# main2.net
KiCad netlist of a schematic drawn in EAGLE
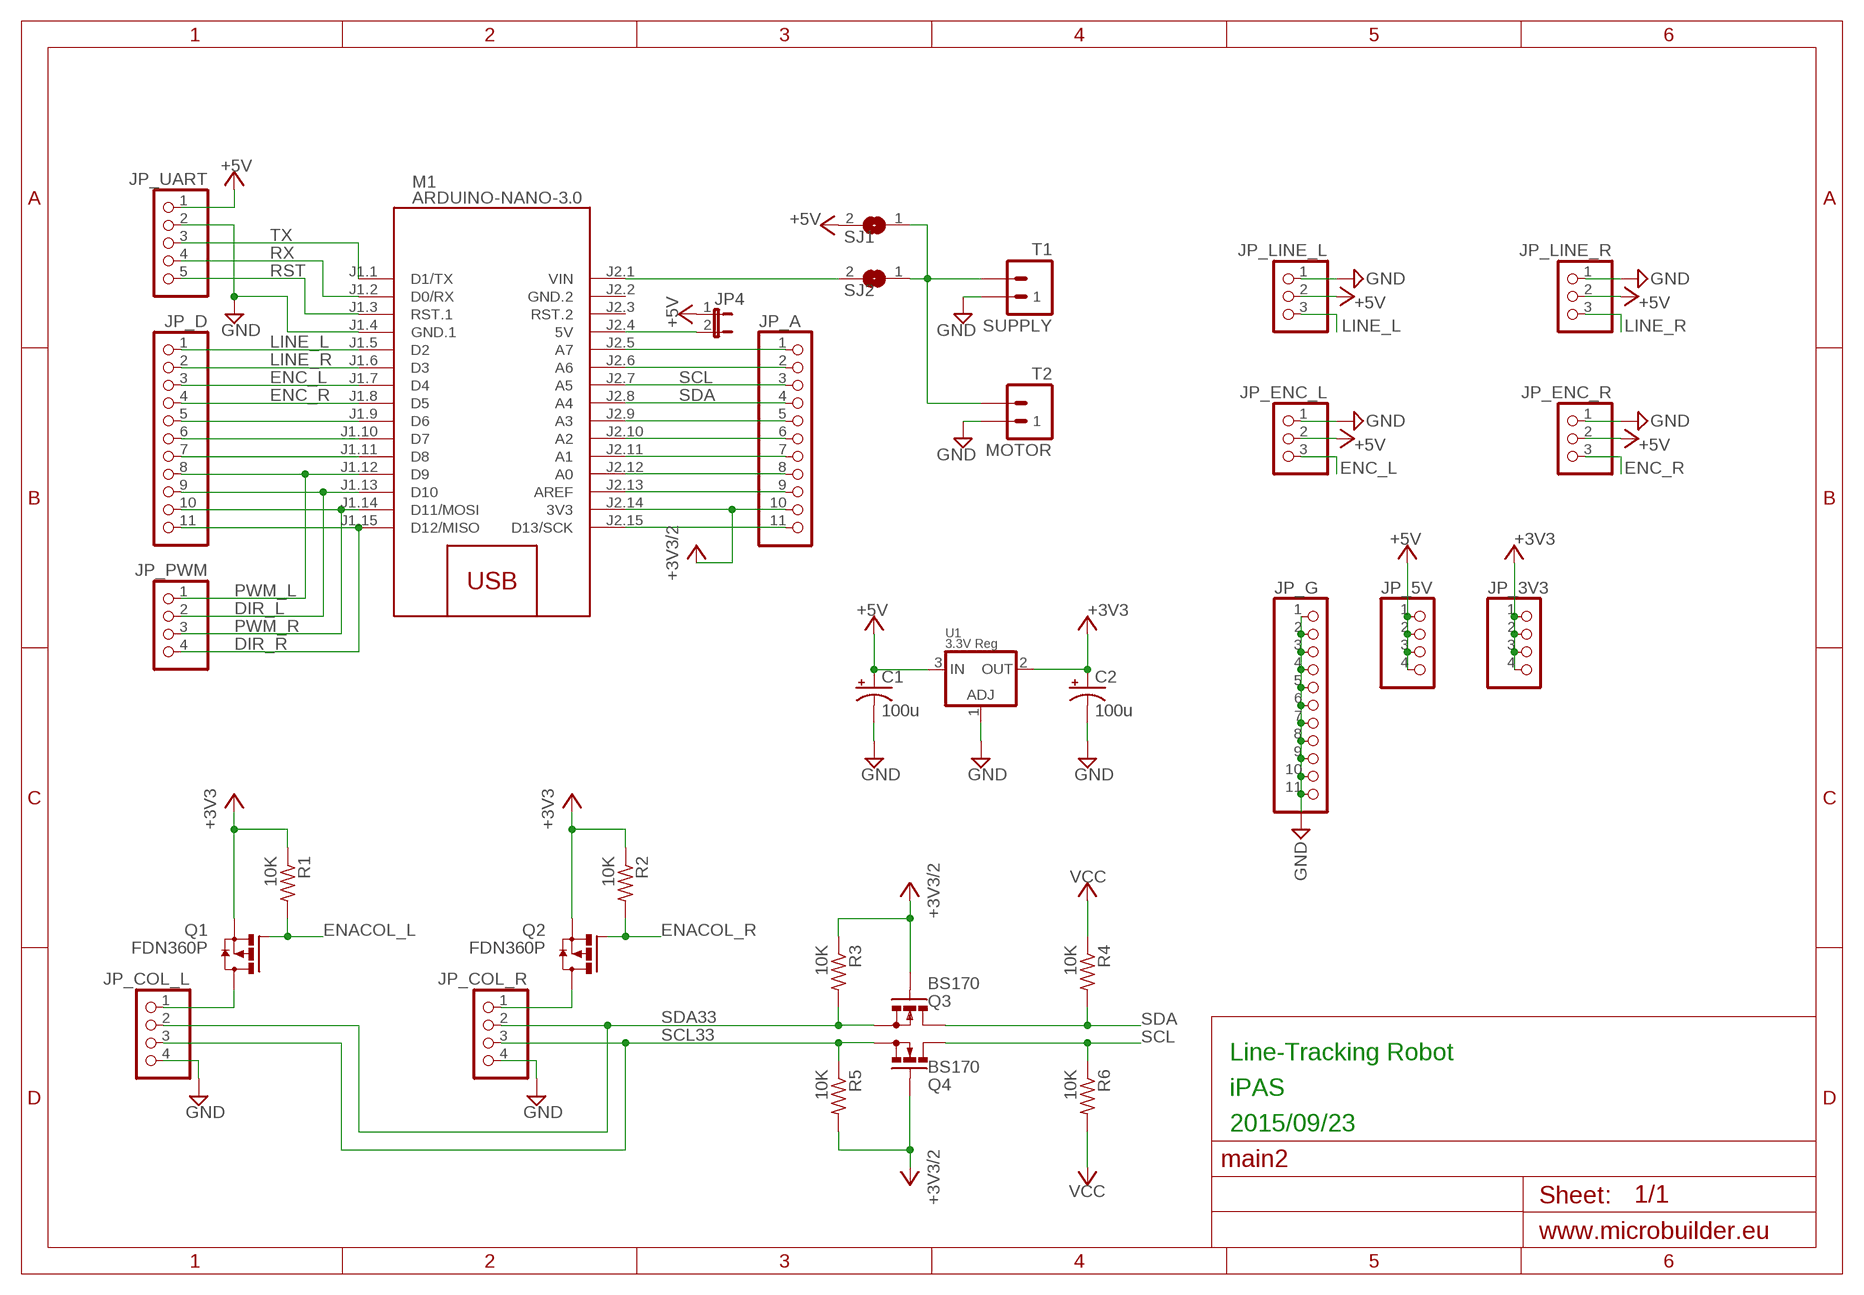
[diagram p0: schematic, sheet 1]

(export (version "E")
  (design (tool "Eeschema 10.0.6"))
  (components
    (comp (ref "C1")
      (value "100u")
      (footprint "eagle-import:RCL_E2,5-6")
      (libsource (lib "eagle-import") (part "RCL_CPOL-USE2.5-6"))
    )
    (comp (ref "C2")
      (value "100u")
      (footprint "eagle-import:RCL_E2,5-6")
      (libsource (lib "eagle-import") (part "RCL_CPOL-USE2.5-6"))
    )
    (comp (ref "JP4")
      (value "JUMPER2")
      (footprint "eagle-import:JUMPER2")
      (libsource (lib "eagle-import") (part "JUMPER2"))
    )
    (comp (ref "JP_3V3")
      (value "HEADER-1X4ROUND")
      (footprint "eagle-import:1X04_ROUND")
      (libsource (lib "eagle-import") (part "HEADER-1X4ROUND"))
    )
    (comp (ref "JP_5V")
      (value "HEADER-1X4ROUND")
      (footprint "eagle-import:1X04_ROUND")
      (libsource (lib "eagle-import") (part "HEADER-1X4ROUND"))
    )
    (comp (ref "JP_A")
      (value "HEADER-1X11")
      (footprint "eagle-import:1X11_ROUND")
      (libsource (lib "eagle-import") (part "HEADER-1X11"))
    )
    (comp (ref "JP_COL_L")
      (value "HEADER-1X4ROUND")
      (footprint "eagle-import:1X04_ROUND")
      (libsource (lib "eagle-import") (part "HEADER-1X4ROUND"))
    )
    (comp (ref "JP_COL_R")
      (value "HEADER-1X4ROUND")
      (footprint "eagle-import:1X04_ROUND")
      (libsource (lib "eagle-import") (part "HEADER-1X4ROUND"))
    )
    (comp (ref "JP_D")
      (value "HEADER-1X11")
      (footprint "eagle-import:1X11_ROUND")
      (libsource (lib "eagle-import") (part "HEADER-1X11"))
    )
    (comp (ref "JP_ENC_L")
      (value "HEADER-1X3ROUND")
      (footprint "eagle-import:1X03_ROUND")
      (libsource (lib "eagle-import") (part "HEADER-1X3ROUND"))
    )
    (comp (ref "JP_ENC_R")
      (value "HEADER-1X3ROUND")
      (footprint "eagle-import:1X03_ROUND")
      (libsource (lib "eagle-import") (part "HEADER-1X3ROUND"))
    )
    (comp (ref "JP_G")
      (value "HEADER-1X11")
      (footprint "eagle-import:1X11_ROUND")
      (libsource (lib "eagle-import") (part "HEADER-1X11"))
    )
    (comp (ref "JP_LINE_L")
      (value "HEADER-1X3ROUND")
      (footprint "eagle-import:1X03_ROUND")
      (libsource (lib "eagle-import") (part "HEADER-1X3ROUND"))
    )
    (comp (ref "JP_LINE_R")
      (value "HEADER-1X3ROUND")
      (footprint "eagle-import:1X03_ROUND")
      (libsource (lib "eagle-import") (part "HEADER-1X3ROUND"))
    )
    (comp (ref "JP_PWM")
      (value "HEADER-1X4ROUND")
      (footprint "eagle-import:1X04_ROUND")
      (libsource (lib "eagle-import") (part "HEADER-1X4ROUND"))
    )
    (comp (ref "JP_UART")
      (value "HEADER-1X5ROUND")
      (footprint "eagle-import:1X05_ROUND")
      (libsource (lib "eagle-import") (part "HEADER-1X5ROUND"))
    )
    (comp (ref "M1")
      (value "ARDUINO-NANO-3.0")
      (footprint "eagle-import:ARDUINO-NANO-3.0")
      (libsource (lib "eagle-import") (part "ARDUINO-NANO-3.0"))
    )
    (comp (ref "Q1")
      (value "FDN360P")
      (footprint "eagle-import:SUPER-SOT3")
      (libsource (lib "eagle-import") (part "FDN360P"))
    )
    (comp (ref "Q2")
      (value "FDN360P")
      (footprint "eagle-import:SUPER-SOT3")
      (libsource (lib "eagle-import") (part "FDN360P"))
    )
    (comp (ref "Q3")
      (value "BS170")
      (footprint "eagle-import:TO92-")
      (libsource (lib "eagle-import") (part "BS170"))
    )
    (comp (ref "Q4")
      (value "BS170")
      (footprint "eagle-import:TO92-")
      (libsource (lib "eagle-import") (part "BS170"))
    )
    (comp (ref "R1")
      (value "10K")
      (footprint "eagle-import:RCL_0204_5")
      (libsource (lib "eagle-import") (part "RCL_R-US0204/5"))
    )
    (comp (ref "R2")
      (value "10K")
      (footprint "eagle-import:RCL_0204_5")
      (libsource (lib "eagle-import") (part "RCL_R-US0204/5"))
    )
    (comp (ref "R3")
      (value "10K")
      (footprint "eagle-import:RCL_0204_5")
      (libsource (lib "eagle-import") (part "RCL_R-US0204/5"))
    )
    (comp (ref "R4")
      (value "10K")
      (footprint "eagle-import:RCL_0204_5")
      (libsource (lib "eagle-import") (part "RCL_R-US0204/5"))
    )
    (comp (ref "R5")
      (value "10K")
      (footprint "eagle-import:RCL_0204_5")
      (libsource (lib "eagle-import") (part "RCL_R-US0204/5"))
    )
    (comp (ref "R6")
      (value "10K")
      (footprint "eagle-import:RCL_0204_5")
      (libsource (lib "eagle-import") (part "RCL_R-US0204/5"))
    )
    (comp (ref "SJ1")
      (value "SOLDERJUMPERREFLOW")
      (footprint "eagle-import:SOLDERJUMPER_REFLOW")
      (libsource (lib "eagle-import") (part "SOLDERJUMPERREFLOW"))
    )
    (comp (ref "SJ2")
      (value "SOLDERJUMPERREFLOW")
      (footprint "eagle-import:SOLDERJUMPER_REFLOW")
      (libsource (lib "eagle-import") (part "SOLDERJUMPERREFLOW"))
    )
    (comp (ref "T1")
      (value "SUPPLY")
      (footprint "eagle-import:DG381-02P")
      (libsource (lib "eagle-import") (part "ST02-3.81MM"))
    )
    (comp (ref "T2")
      (value "MOTOR")
      (footprint "eagle-import:DG381-02P")
      (libsource (lib "eagle-import") (part "ST02-3.81MM"))
    )
    (comp (ref "U1")
      (value "3.3V Reg")
      (footprint "eagle-import:SOT223-R")
      (libsource (lib "eagle-import") (part "LM1117SOT223-REFLOW"))
    )
  )
  (nets
    (net (code "1") (name "+3V3") (class "Default")
      (node (ref "C2") (pin "+") (pinfunction "+_+") (pintype "passive"))
      (node (ref "JP_3V3") (pin "1") (pinfunction "1_1") (pintype "passive"))
      (node (ref "JP_3V3") (pin "2") (pinfunction "2_2") (pintype "passive"))
      (node (ref "JP_3V3") (pin "3") (pinfunction "3_3") (pintype "passive"))
      (node (ref "JP_3V3") (pin "4") (pinfunction "4_4") (pintype "passive"))
      (node (ref "Q1") (pin "2") (pinfunction "S_2") (pintype "passive"))
      (node (ref "Q2") (pin "2") (pinfunction "S_2") (pintype "passive"))
      (node (ref "R1") (pin "1") (pinfunction "1_1") (pintype "passive"))
      (node (ref "R2") (pin "1") (pinfunction "1_1") (pintype "passive"))
      (node (ref "U1") (pin "2") (pinfunction "OUT_2") (pintype "passive"))
    )
    (net (code "2") (name "+3V3{slash}2") (class "Default")
      (node (ref "JP_A") (pin "10") (pinfunction "10_10") (pintype "passive"))
      (node (ref "M1") (pin "J2.14") (pinfunction "3V3_J2.14") (pintype "power_in"))
      (node (ref "Q3") (pin "2") (pinfunction "G_2") (pintype "passive"))
      (node (ref "Q4") (pin "2") (pinfunction "G_2") (pintype "passive"))
      (node (ref "R3") (pin "1") (pinfunction "1_1") (pintype "passive"))
      (node (ref "R5") (pin "2") (pinfunction "2_2") (pintype "passive"))
    )
    (net (code "3") (name "+5V") (class "Default")
      (node (ref "C1") (pin "+") (pinfunction "+_+") (pintype "passive"))
      (node (ref "JP4") (pin "1") (pinfunction "1_1") (pintype "passive"))
      (node (ref "JP_5V") (pin "1") (pinfunction "1_1") (pintype "passive"))
      (node (ref "JP_5V") (pin "2") (pinfunction "2_2") (pintype "passive"))
      (node (ref "JP_5V") (pin "3") (pinfunction "3_3") (pintype "passive"))
      (node (ref "JP_5V") (pin "4") (pinfunction "4_4") (pintype "passive"))
      (node (ref "JP_ENC_L") (pin "2") (pinfunction "2_2") (pintype "passive"))
      (node (ref "JP_ENC_R") (pin "2") (pinfunction "2_2") (pintype "passive"))
      (node (ref "JP_LINE_L") (pin "2") (pinfunction "2_2") (pintype "passive"))
      (node (ref "JP_LINE_R") (pin "2") (pinfunction "2_2") (pintype "passive"))
      (node (ref "JP_UART") (pin "1") (pinfunction "1_1") (pintype "passive"))
      (node (ref "SJ1") (pin "2") (pinfunction "2_2") (pintype "passive"))
      (node (ref "U1") (pin "3") (pinfunction "IN_3") (pintype "input"))
    )
    (net (code "4") (name "/DIR_L") (class "Default")
      (node (ref "JP_D") (pin "9") (pinfunction "9_9") (pintype "passive"))
      (node (ref "JP_PWM") (pin "2") (pinfunction "2_2") (pintype "passive"))
      (node (ref "M1") (pin "J1.13") (pinfunction "D10_J1.13") (pintype "bidirectional"))
    )
    (net (code "5") (name "/DIR_R") (class "Default")
      (node (ref "JP_D") (pin "11") (pinfunction "11_11") (pintype "passive"))
      (node (ref "JP_PWM") (pin "4") (pinfunction "4_4") (pintype "passive"))
      (node (ref "M1") (pin "J1.15") (pinfunction "D12/MISO_J1.15") (pintype "bidirectional"))
    )
    (net (code "6") (name "/ENACOL_L") (class "Default")
      (node (ref "Q1") (pin "1") (pinfunction "G_1") (pintype "passive"))
      (node (ref "R1") (pin "2") (pinfunction "2_2") (pintype "passive"))
    )
    (net (code "7") (name "/ENACOL_R") (class "Default")
      (node (ref "Q2") (pin "1") (pinfunction "G_1") (pintype "passive"))
      (node (ref "R2") (pin "2") (pinfunction "2_2") (pintype "passive"))
    )
    (net (code "8") (name "/ENC_L") (class "Default")
      (node (ref "JP_D") (pin "3") (pinfunction "3_3") (pintype "passive"))
      (node (ref "JP_ENC_L") (pin "3") (pinfunction "3_3") (pintype "passive"))
      (node (ref "M1") (pin "J1.7") (pinfunction "D4_J1.7") (pintype "bidirectional"))
    )
    (net (code "9") (name "/ENC_R") (class "Default")
      (node (ref "JP_D") (pin "4") (pinfunction "4_4") (pintype "passive"))
      (node (ref "JP_ENC_R") (pin "3") (pinfunction "3_3") (pintype "passive"))
      (node (ref "M1") (pin "J1.8") (pinfunction "D5_J1.8") (pintype "bidirectional"))
    )
    (net (code "10") (name "/GND.2") (class "Default")
      (node (ref "M1") (pin "J2.2") (pinfunction "GND.2_J2.2") (pintype "power_in"))
    )
    (net (code "11") (name "/LINE_L") (class "Default")
      (node (ref "JP_D") (pin "1") (pinfunction "1_1") (pintype "passive"))
      (node (ref "JP_LINE_L") (pin "3") (pinfunction "3_3") (pintype "passive"))
      (node (ref "M1") (pin "J1.5") (pinfunction "D2_J1.5") (pintype "bidirectional"))
    )
    (net (code "12") (name "/LINE_R") (class "Default")
      (node (ref "JP_D") (pin "2") (pinfunction "2_2") (pintype "passive"))
      (node (ref "JP_LINE_R") (pin "3") (pinfunction "3_3") (pintype "passive"))
      (node (ref "M1") (pin "J1.6") (pinfunction "D3_J1.6") (pintype "bidirectional"))
    )
    (net (code "13") (name "/PWM_L") (class "Default")
      (node (ref "JP_D") (pin "8") (pinfunction "8_8") (pintype "passive"))
      (node (ref "JP_PWM") (pin "1") (pinfunction "1_1") (pintype "passive"))
      (node (ref "M1") (pin "J1.12") (pinfunction "D9_J1.12") (pintype "bidirectional"))
    )
    (net (code "14") (name "/PWM_R") (class "Default")
      (node (ref "JP_D") (pin "10") (pinfunction "10_10") (pintype "passive"))
      (node (ref "JP_PWM") (pin "3") (pinfunction "3_3") (pintype "passive"))
      (node (ref "M1") (pin "J1.14") (pinfunction "D11/MOSI_J1.14") (pintype "bidirectional"))
    )
    (net (code "15") (name "/RST") (class "Default")
      (node (ref "JP_UART") (pin "5") (pinfunction "5_5") (pintype "passive"))
      (node (ref "M1") (pin "J1.3") (pinfunction "RST.1_J1.3") (pintype "bidirectional"))
    )
    (net (code "16") (name "/RX") (class "Default")
      (node (ref "JP_UART") (pin "4") (pinfunction "4_4") (pintype "passive"))
      (node (ref "M1") (pin "J1.2") (pinfunction "D0/RX_J1.2") (pintype "bidirectional"))
    )
    (net (code "17") (name "/SCL") (class "Default")
      (node (ref "JP_A") (pin "3") (pinfunction "3_3") (pintype "passive"))
      (node (ref "M1") (pin "J2.7") (pinfunction "A5_J2.7") (pintype "bidirectional"))
      (node (ref "Q4") (pin "1") (pinfunction "D_1") (pintype "passive"))
      (node (ref "R6") (pin "1") (pinfunction "1_1") (pintype "passive"))
    )
    (net (code "18") (name "/SCL33") (class "Default")
      (node (ref "JP_COL_L") (pin "3") (pinfunction "3_3") (pintype "passive"))
      (node (ref "JP_COL_R") (pin "3") (pinfunction "3_3") (pintype "passive"))
      (node (ref "Q4") (pin "3") (pinfunction "S_3") (pintype "passive"))
      (node (ref "R5") (pin "1") (pinfunction "1_1") (pintype "passive"))
    )
    (net (code "19") (name "/SDA") (class "Default")
      (node (ref "JP_A") (pin "4") (pinfunction "4_4") (pintype "passive"))
      (node (ref "M1") (pin "J2.8") (pinfunction "A4_J2.8") (pintype "bidirectional"))
      (node (ref "Q3") (pin "1") (pinfunction "D_1") (pintype "passive"))
      (node (ref "R4") (pin "2") (pinfunction "2_2") (pintype "passive"))
    )
    (net (code "20") (name "/SDA33") (class "Default")
      (node (ref "JP_COL_L") (pin "2") (pinfunction "2_2") (pintype "passive"))
      (node (ref "JP_COL_R") (pin "2") (pinfunction "2_2") (pintype "passive"))
      (node (ref "Q3") (pin "3") (pinfunction "S_3") (pintype "passive"))
      (node (ref "R3") (pin "2") (pinfunction "2_2") (pintype "passive"))
    )
    (net (code "21") (name "/TX") (class "Default")
      (node (ref "JP_UART") (pin "3") (pinfunction "3_3") (pintype "passive"))
      (node (ref "M1") (pin "J1.1") (pinfunction "D1/TX_J1.1") (pintype "bidirectional"))
    )
    (net (code "22") (name "GND") (class "Default")
      (node (ref "C1") (pin "-") (pinfunction "-_-") (pintype "passive"))
      (node (ref "C2") (pin "-") (pinfunction "-_-") (pintype "passive"))
      (node (ref "JP_COL_L") (pin "4") (pinfunction "4_4") (pintype "passive"))
      (node (ref "JP_COL_R") (pin "4") (pinfunction "4_4") (pintype "passive"))
      (node (ref "JP_ENC_L") (pin "1") (pinfunction "1_1") (pintype "passive"))
      (node (ref "JP_ENC_R") (pin "1") (pinfunction "1_1") (pintype "passive"))
      (node (ref "JP_G") (pin "1") (pinfunction "1_1") (pintype "passive"))
      (node (ref "JP_G") (pin "10") (pinfunction "10_10") (pintype "passive"))
      (node (ref "JP_G") (pin "11") (pinfunction "11_11") (pintype "passive"))
      (node (ref "JP_G") (pin "2") (pinfunction "2_2") (pintype "passive"))
      (node (ref "JP_G") (pin "3") (pinfunction "3_3") (pintype "passive"))
      (node (ref "JP_G") (pin "4") (pinfunction "4_4") (pintype "passive"))
      (node (ref "JP_G") (pin "5") (pinfunction "5_5") (pintype "passive"))
      (node (ref "JP_G") (pin "6") (pinfunction "6_6") (pintype "passive"))
      (node (ref "JP_G") (pin "7") (pinfunction "7_7") (pintype "passive"))
      (node (ref "JP_G") (pin "8") (pinfunction "8_8") (pintype "passive"))
      (node (ref "JP_G") (pin "9") (pinfunction "9_9") (pintype "passive"))
      (node (ref "JP_LINE_L") (pin "1") (pinfunction "1_1") (pintype "passive"))
      (node (ref "JP_LINE_R") (pin "1") (pinfunction "1_1") (pintype "passive"))
      (node (ref "JP_UART") (pin "2") (pinfunction "2_2") (pintype "passive"))
      (node (ref "M1") (pin "J1.4") (pinfunction "GND.1_J1.4") (pintype "power_in"))
      (node (ref "T1") (pin "1") (pinfunction "1_1") (pintype "passive"))
      (node (ref "T2") (pin "1") (pinfunction "1_1") (pintype "passive"))
      (node (ref "U1") (pin "1") (pinfunction "ADJ_1") (pintype "input"))
    )
    (net (code "23") (name "Net-(M1-5V)") (class "Default")
      (node (ref "JP4") (pin "2") (pinfunction "2_2") (pintype "passive"))
      (node (ref "M1") (pin "J2.4") (pinfunction "5V_J2.4") (pintype "power_in"))
    )
    (net (code "24") (name "Net-(M1-A0)") (class "Default")
      (node (ref "JP_A") (pin "8") (pinfunction "8_8") (pintype "passive"))
      (node (ref "M1") (pin "J2.12") (pinfunction "A0_J2.12") (pintype "bidirectional"))
    )
    (net (code "25") (name "Net-(M1-A1)") (class "Default")
      (node (ref "JP_A") (pin "7") (pinfunction "7_7") (pintype "passive"))
      (node (ref "M1") (pin "J2.11") (pinfunction "A1_J2.11") (pintype "bidirectional"))
    )
    (net (code "26") (name "Net-(M1-A2)") (class "Default")
      (node (ref "JP_A") (pin "6") (pinfunction "6_6") (pintype "passive"))
      (node (ref "M1") (pin "J2.10") (pinfunction "A2_J2.10") (pintype "bidirectional"))
    )
    (net (code "27") (name "Net-(M1-A3)") (class "Default")
      (node (ref "JP_A") (pin "5") (pinfunction "5_5") (pintype "passive"))
      (node (ref "M1") (pin "J2.9") (pinfunction "A3_J2.9") (pintype "bidirectional"))
    )
    (net (code "28") (name "Net-(M1-A6)") (class "Default")
      (node (ref "JP_A") (pin "2") (pinfunction "2_2") (pintype "passive"))
      (node (ref "M1") (pin "J2.6") (pinfunction "A6_J2.6") (pintype "bidirectional"))
    )
    (net (code "29") (name "Net-(M1-A7)") (class "Default")
      (node (ref "JP_A") (pin "1") (pinfunction "1_1") (pintype "passive"))
      (node (ref "M1") (pin "J2.5") (pinfunction "A7_J2.5") (pintype "bidirectional"))
    )
    (net (code "30") (name "Net-(M1-AREF)") (class "Default")
      (node (ref "JP_A") (pin "9") (pinfunction "9_9") (pintype "passive"))
      (node (ref "M1") (pin "J2.13") (pinfunction "AREF_J2.13") (pintype "bidirectional"))
    )
    (net (code "31") (name "Net-(M1-D6)") (class "Default")
      (node (ref "JP_D") (pin "5") (pinfunction "5_5") (pintype "passive"))
      (node (ref "M1") (pin "J1.9") (pinfunction "D6_J1.9") (pintype "bidirectional"))
    )
    (net (code "32") (name "Net-(M1-D7)") (class "Default")
      (node (ref "JP_D") (pin "6") (pinfunction "6_6") (pintype "passive"))
      (node (ref "M1") (pin "J1.10") (pinfunction "D7_J1.10") (pintype "bidirectional"))
    )
    (net (code "33") (name "Net-(M1-D8)") (class "Default")
      (node (ref "JP_D") (pin "7") (pinfunction "7_7") (pintype "passive"))
      (node (ref "M1") (pin "J1.11") (pinfunction "D8_J1.11") (pintype "bidirectional"))
    )
    (net (code "34") (name "Net-(M1-D13{slash}SCK)") (class "Default")
      (node (ref "JP_A") (pin "11") (pinfunction "11_11") (pintype "passive"))
      (node (ref "M1") (pin "J2.15") (pinfunction "D13/SCK_J2.15") (pintype "bidirectional"))
    )
    (net (code "35") (name "Net-(M1-VIN)") (class "Default")
      (node (ref "M1") (pin "J2.1") (pinfunction "VIN_J2.1") (pintype "power_in"))
      (node (ref "SJ2") (pin "2") (pinfunction "2_2") (pintype "passive"))
    )
    (net (code "36") (name "Net-(Q1-D)") (class "Default")
      (node (ref "JP_COL_L") (pin "1") (pinfunction "1_1") (pintype "passive"))
      (node (ref "Q1") (pin "3") (pinfunction "D_3") (pintype "passive"))
    )
    (net (code "37") (name "Net-(Q2-D)") (class "Default")
      (node (ref "JP_COL_R") (pin "1") (pinfunction "1_1") (pintype "passive"))
      (node (ref "Q2") (pin "3") (pinfunction "D_3") (pintype "passive"))
    )
    (net (code "38") (name "Net-(SJ1-Pad1)") (class "Default")
      (node (ref "SJ1") (pin "1") (pinfunction "1_1") (pintype "passive"))
      (node (ref "SJ2") (pin "1") (pinfunction "1_1") (pintype "passive"))
      (node (ref "T1") (pin "2") (pinfunction "2_2") (pintype "passive"))
      (node (ref "T2") (pin "2") (pinfunction "2_2") (pintype "passive"))
    )
    (net (code "39") (name "VCC") (class "Default")
      (node (ref "R4") (pin "1") (pinfunction "1_1") (pintype "passive"))
      (node (ref "R6") (pin "2") (pinfunction "2_2") (pintype "passive"))
    )
    (net (code "40") (name "unconnected-(M1-RST.2-PadJ2.3)") (class "Default")
      (node (ref "M1") (pin "J2.3") (pinfunction "RST.2_J2.3") (pintype "bidirectional"))
    )
  )
)
